# CITestShield.net
KiCad netlist of a schematic drawn in EAGLE
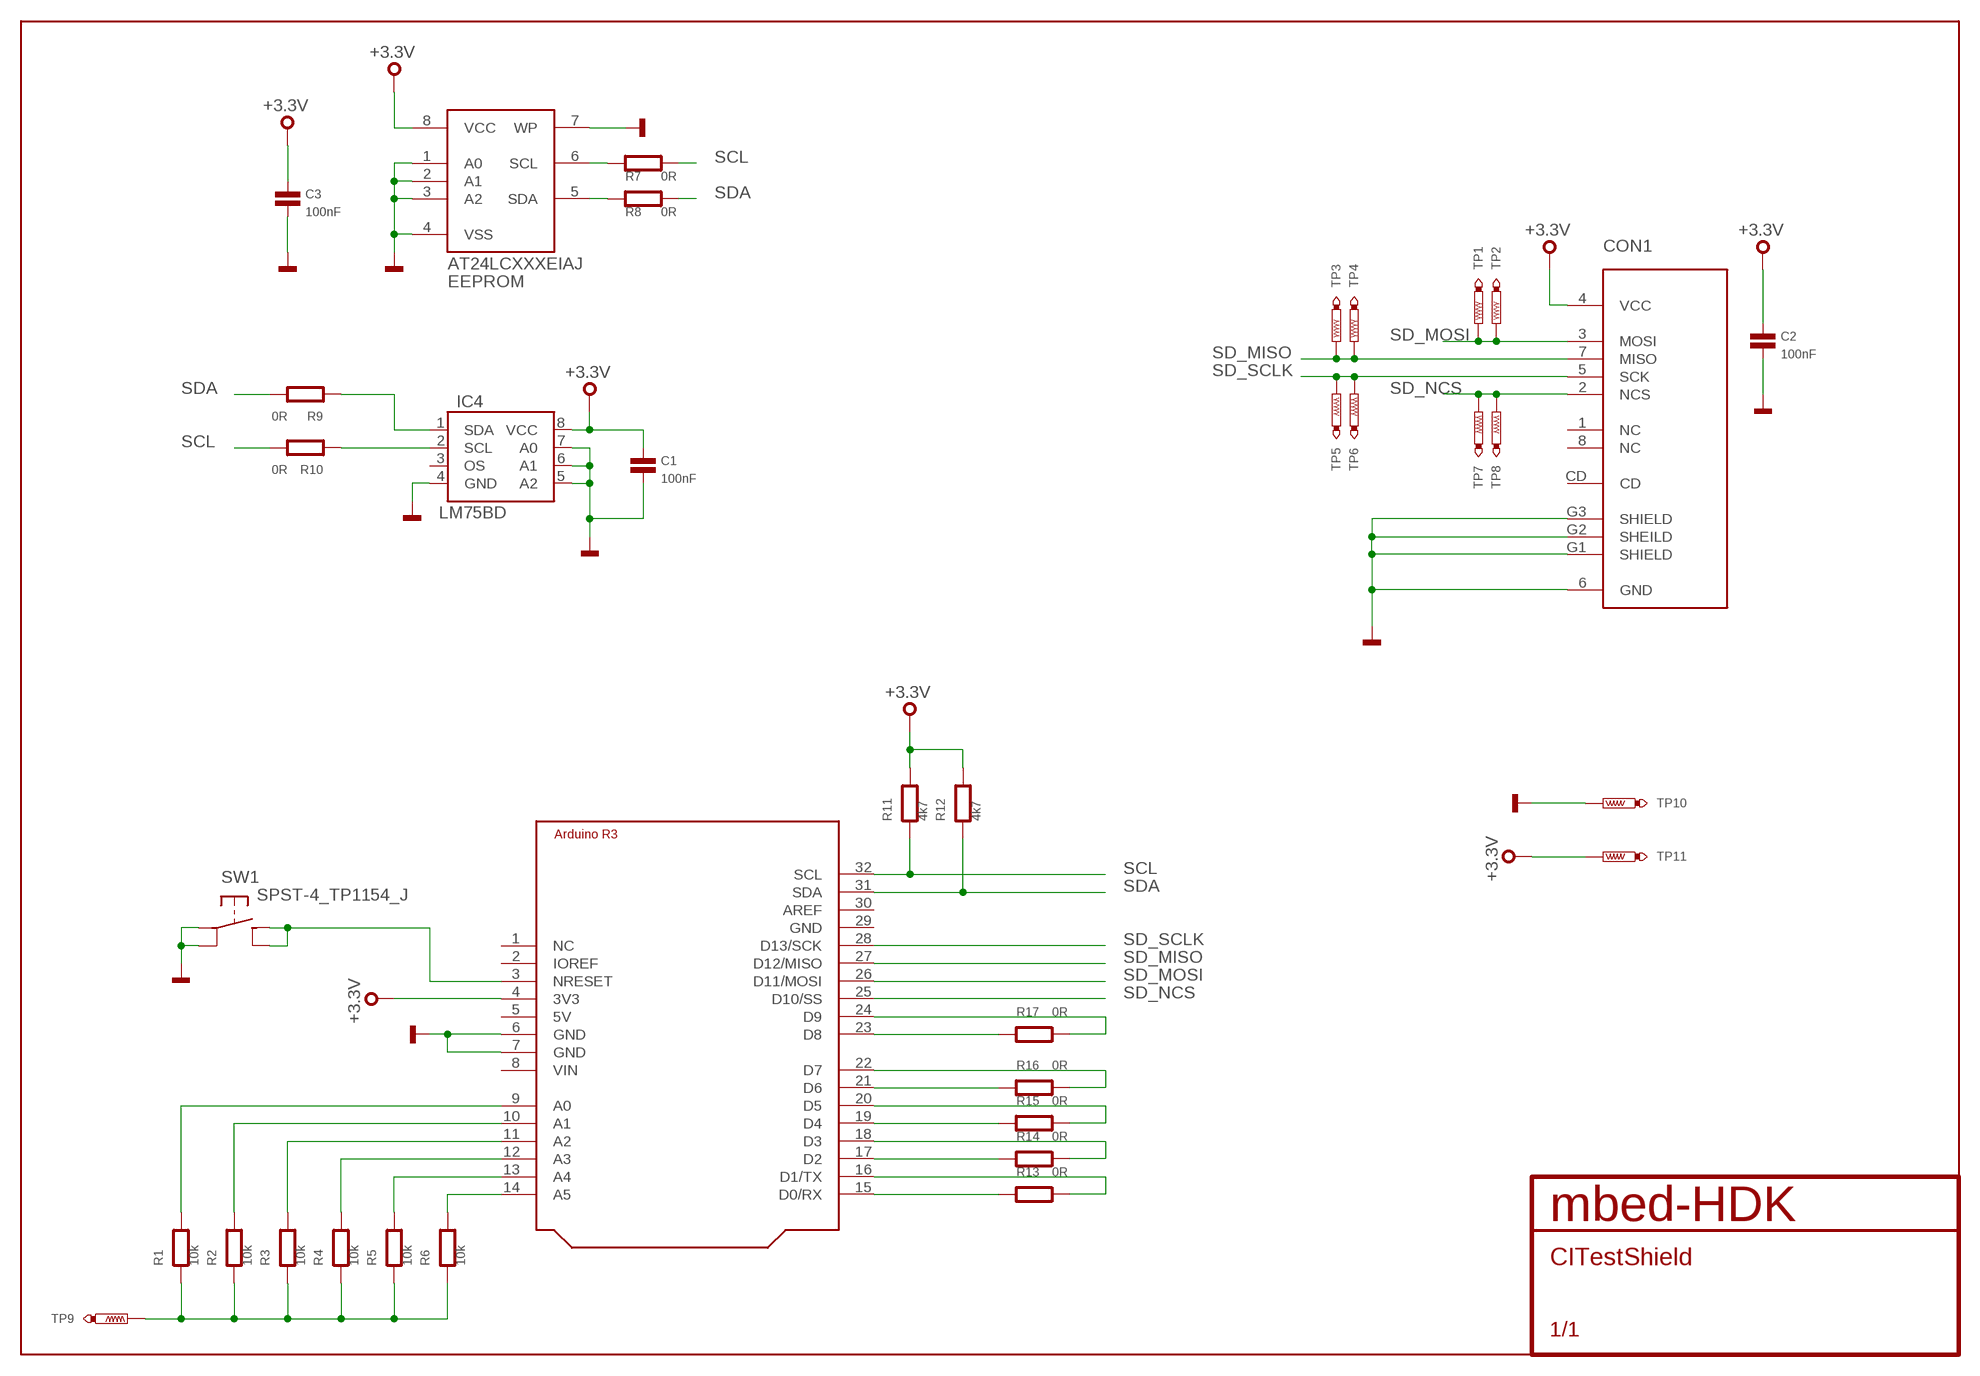
[diagram p0: schematic, sheet 1]

(export (version "E")
  (design (tool "Eeschema 10.0.6"))
  (components
    (comp (ref "BRD1")
      (value "ARDUINO-R3_SILK")
      (footprint "eagle-import:ARDUINO-R3-SILK")
      (libsource (lib "eagle-import") (part "ARDUINO-R3_SILK"))
    )
    (comp (ref "C1")
      (value "100nF")
      (footprint "eagle-import:0603")
      (libsource (lib "eagle-import") (part "C0603"))
    )
    (comp (ref "C2")
      (value "100nF")
      (footprint "eagle-import:0603")
      (libsource (lib "eagle-import") (part "C0603"))
    )
    (comp (ref "C3")
      (value "100nF")
      (footprint "eagle-import:0603")
      (libsource (lib "eagle-import") (part "C0603"))
    )
    (comp (ref "CON1")
      (value "MICRO-SD")
      (footprint "eagle-import:AMPHENOL-101-00660-68-6")
      (libsource (lib "eagle-import") (part "MICRO-SD"))
    )
    (comp (ref "EEPROM")
      (value "AT24LCXXXEIAJ")
      (footprint "eagle-import:SO08-EIAJ")
      (libsource (lib "eagle-import") (part "AT24LCXXXEIAJ"))
    )
    (comp (ref "IC4")
      (value "LM75BD")
      (footprint "eagle-import:SO8")
      (libsource (lib "eagle-import") (part "LM75BD"))
    )
    (comp (ref "R1")
      (value "10k")
      (footprint "eagle-import:0603")
      (libsource (lib "eagle-import") (part "R0603"))
    )
    (comp (ref "R2")
      (value "10k")
      (footprint "eagle-import:0603")
      (libsource (lib "eagle-import") (part "R0603"))
    )
    (comp (ref "R3")
      (value "10k")
      (footprint "eagle-import:0603")
      (libsource (lib "eagle-import") (part "R0603"))
    )
    (comp (ref "R4")
      (value "10k")
      (footprint "eagle-import:0603")
      (libsource (lib "eagle-import") (part "R0603"))
    )
    (comp (ref "R5")
      (value "10k")
      (footprint "eagle-import:0603")
      (libsource (lib "eagle-import") (part "R0603"))
    )
    (comp (ref "R6")
      (value "10k")
      (footprint "eagle-import:0603")
      (libsource (lib "eagle-import") (part "R0603"))
    )
    (comp (ref "R7")
      (value "0R")
      (footprint "eagle-import:0603")
      (libsource (lib "eagle-import") (part "R0603"))
    )
    (comp (ref "R8")
      (value "0R")
      (footprint "eagle-import:0603")
      (libsource (lib "eagle-import") (part "R0603"))
    )
    (comp (ref "R9")
      (value "0R")
      (footprint "eagle-import:0603")
      (libsource (lib "eagle-import") (part "R0603"))
    )
    (comp (ref "R10")
      (value "0R")
      (footprint "eagle-import:0603")
      (libsource (lib "eagle-import") (part "R0603"))
    )
    (comp (ref "R11")
      (value "4k7")
      (footprint "eagle-import:0603")
      (libsource (lib "eagle-import") (part "R0603"))
    )
    (comp (ref "R12")
      (value "4k7")
      (footprint "eagle-import:0603")
      (libsource (lib "eagle-import") (part "R0603"))
    )
    (comp (ref "R13")
      (value "0R")
      (footprint "eagle-import:0603")
      (libsource (lib "eagle-import") (part "R0603"))
    )
    (comp (ref "R14")
      (value "0R")
      (footprint "eagle-import:0603")
      (libsource (lib "eagle-import") (part "R0603"))
    )
    (comp (ref "R15")
      (value "0R")
      (footprint "eagle-import:0603")
      (libsource (lib "eagle-import") (part "R0603"))
    )
    (comp (ref "R16")
      (value "0R")
      (footprint "eagle-import:0603")
      (libsource (lib "eagle-import") (part "R0603"))
    )
    (comp (ref "R17")
      (value "0R")
      (footprint "eagle-import:0603")
      (libsource (lib "eagle-import") (part "R0603"))
    )
    (comp (ref "SW1")
      (value "SPST-4_TP1154_J")
      (footprint "eagle-import:TP-1154X")
      (libsource (lib "eagle-import") (part "SPST-4_TP1154_J"))
    )
    (comp (ref "TP1")
      (value "TEST-POINT-50R-SMD")
      (footprint "eagle-import:TP50-SMD")
      (libsource (lib "eagle-import") (part "TEST-POINT-50R-SMD"))
    )
    (comp (ref "TP2")
      (value "TEST-POINT-50R-SMD")
      (footprint "eagle-import:TP50-SMD")
      (libsource (lib "eagle-import") (part "TEST-POINT-50R-SMD"))
    )
    (comp (ref "TP3")
      (value "TEST-POINT-50R-SMD")
      (footprint "eagle-import:TP50-SMD")
      (libsource (lib "eagle-import") (part "TEST-POINT-50R-SMD"))
    )
    (comp (ref "TP4")
      (value "TEST-POINT-50R-SMD")
      (footprint "eagle-import:TP50-SMD")
      (libsource (lib "eagle-import") (part "TEST-POINT-50R-SMD"))
    )
    (comp (ref "TP5")
      (value "TEST-POINT-50R-SMD")
      (footprint "eagle-import:TP50-SMD")
      (libsource (lib "eagle-import") (part "TEST-POINT-50R-SMD"))
    )
    (comp (ref "TP6")
      (value "TEST-POINT-50R-SMD")
      (footprint "eagle-import:TP50-SMD")
      (libsource (lib "eagle-import") (part "TEST-POINT-50R-SMD"))
    )
    (comp (ref "TP7")
      (value "TEST-POINT-50R-SMD")
      (footprint "eagle-import:TP50-SMD")
      (libsource (lib "eagle-import") (part "TEST-POINT-50R-SMD"))
    )
    (comp (ref "TP8")
      (value "TEST-POINT-50R-SMD")
      (footprint "eagle-import:TP50-SMD")
      (libsource (lib "eagle-import") (part "TEST-POINT-50R-SMD"))
    )
    (comp (ref "TP9")
      (value "TEST-POINT-50R-SMD")
      (footprint "eagle-import:TP50-SMD")
      (libsource (lib "eagle-import") (part "TEST-POINT-50R-SMD"))
    )
    (comp (ref "TP10")
      (value "TEST-POINT-50R-SMD")
      (footprint "eagle-import:TP50-SMD")
      (libsource (lib "eagle-import") (part "TEST-POINT-50R-SMD"))
    )
    (comp (ref "TP11")
      (value "TEST-POINT-50R-SMD")
      (footprint "eagle-import:TP50-SMD")
      (libsource (lib "eagle-import") (part "TEST-POINT-50R-SMD"))
    )
  )
  (nets
    (net (code "1") (name "+3.3V") (class "Default")
      (node (ref "BRD1") (pin "4") (pinfunction "3V3_4") (pintype "bidirectional"))
      (node (ref "C1") (pin "1") (pinfunction "P$1_1") (pintype "passive"))
      (node (ref "C2") (pin "1") (pinfunction "P$1_1") (pintype "passive"))
      (node (ref "C3") (pin "1") (pinfunction "P$1_1") (pintype "passive"))
      (node (ref "CON1") (pin "4") (pinfunction "VCC_4") (pintype "bidirectional"))
      (node (ref "EEPROM") (pin "8") (pinfunction "VCC_8") (pintype "power_in"))
      (node (ref "IC4") (pin "8") (pinfunction "VCC_8") (pintype "bidirectional"))
      (node (ref "R11") (pin "2") (pinfunction "P$2_2") (pintype "passive"))
      (node (ref "R12") (pin "2") (pinfunction "P$2_2") (pintype "passive"))
      (node (ref "TP11") (pin "TP") (pinfunction "TP_TP") (pintype "input"))
    )
    (net (code "2") (name "/SCL") (class "Default")
      (node (ref "BRD1") (pin "32") (pinfunction "SCL_32") (pintype "bidirectional"))
      (node (ref "R10") (pin "2") (pinfunction "P$2_2") (pintype "passive"))
      (node (ref "R11") (pin "1") (pinfunction "P$1_1") (pintype "passive"))
      (node (ref "R7") (pin "2") (pinfunction "P$2_2") (pintype "passive"))
    )
    (net (code "3") (name "/SDA") (class "Default")
      (node (ref "BRD1") (pin "31") (pinfunction "SDA_31") (pintype "bidirectional"))
      (node (ref "R12") (pin "1") (pinfunction "P$1_1") (pintype "passive"))
      (node (ref "R8") (pin "2") (pinfunction "P$2_2") (pintype "passive"))
      (node (ref "R9") (pin "2") (pinfunction "P$2_2") (pintype "passive"))
    )
    (net (code "4") (name "/SD_MISO") (class "Default")
      (node (ref "BRD1") (pin "27") (pinfunction "D12/MISO_27") (pintype "bidirectional"))
      (node (ref "CON1") (pin "7") (pinfunction "MISO_7") (pintype "bidirectional"))
      (node (ref "TP3") (pin "TP") (pinfunction "TP_TP") (pintype "input"))
      (node (ref "TP4") (pin "TP") (pinfunction "TP_TP") (pintype "input"))
    )
    (net (code "5") (name "/SD_MOSI") (class "Default")
      (node (ref "BRD1") (pin "26") (pinfunction "D11/MOSI_26") (pintype "bidirectional"))
      (node (ref "CON1") (pin "3") (pinfunction "MOSI_3") (pintype "bidirectional"))
      (node (ref "TP1") (pin "TP") (pinfunction "TP_TP") (pintype "input"))
      (node (ref "TP2") (pin "TP") (pinfunction "TP_TP") (pintype "input"))
    )
    (net (code "6") (name "/SD_NCS") (class "Default")
      (node (ref "BRD1") (pin "25") (pinfunction "D10/SS_25") (pintype "bidirectional"))
      (node (ref "CON1") (pin "2") (pinfunction "NCS_2") (pintype "bidirectional"))
      (node (ref "TP7") (pin "TP") (pinfunction "TP_TP") (pintype "input"))
      (node (ref "TP8") (pin "TP") (pinfunction "TP_TP") (pintype "input"))
    )
    (net (code "7") (name "/SD_SCLK") (class "Default")
      (node (ref "BRD1") (pin "28") (pinfunction "D13/SCK_28") (pintype "bidirectional"))
      (node (ref "CON1") (pin "5") (pinfunction "SCK_5") (pintype "bidirectional"))
      (node (ref "TP5") (pin "TP") (pinfunction "TP_TP") (pintype "input"))
      (node (ref "TP6") (pin "TP") (pinfunction "TP_TP") (pintype "input"))
    )
    (net (code "8") (name "GND") (class "Default")
      (node (ref "BRD1") (pin "6") (pinfunction "GND_6") (pintype "bidirectional"))
      (node (ref "BRD1") (pin "7") (pinfunction "GND_7") (pintype "bidirectional"))
      (node (ref "C1") (pin "2") (pinfunction "P$2_2") (pintype "passive"))
      (node (ref "C2") (pin "2") (pinfunction "P$2_2") (pintype "passive"))
      (node (ref "C3") (pin "2") (pinfunction "P$2_2") (pintype "passive"))
      (node (ref "CON1") (pin "6") (pinfunction "GND_6") (pintype "bidirectional"))
      (node (ref "CON1") (pin "G1") (pinfunction "SHIELD_G1") (pintype "bidirectional"))
      (node (ref "CON1") (pin "G2") (pinfunction "SHEILD_G2") (pintype "bidirectional"))
      (node (ref "CON1") (pin "G3") (pinfunction "SHIELD_G3") (pintype "bidirectional"))
      (node (ref "EEPROM") (pin "1") (pinfunction "A0_1") (pintype "bidirectional"))
      (node (ref "EEPROM") (pin "2") (pinfunction "A1_2") (pintype "bidirectional"))
      (node (ref "EEPROM") (pin "3") (pinfunction "A2_3") (pintype "bidirectional"))
      (node (ref "EEPROM") (pin "4") (pinfunction "VSS_4") (pintype "power_in"))
      (node (ref "EEPROM") (pin "7") (pinfunction "WP_7") (pintype "bidirectional"))
      (node (ref "IC4") (pin "4") (pinfunction "GND_4") (pintype "bidirectional"))
      (node (ref "IC4") (pin "5") (pinfunction "A2_5") (pintype "bidirectional"))
      (node (ref "IC4") (pin "6") (pinfunction "A1_6") (pintype "bidirectional"))
      (node (ref "IC4") (pin "7") (pinfunction "A0_7") (pintype "bidirectional"))
      (node (ref "SW1") (pin "A1") (pinfunction "A1_A1") (pintype "passive"))
      (node (ref "SW1") (pin "A2") (pinfunction "A2_A2") (pintype "passive"))
      (node (ref "TP10") (pin "TP") (pinfunction "TP_TP") (pintype "input"))
    )
    (net (code "9") (name "Net-(BRD1-A0)") (class "Default")
      (node (ref "BRD1") (pin "9") (pinfunction "A0_9") (pintype "bidirectional"))
      (node (ref "R1") (pin "2") (pinfunction "P$2_2") (pintype "passive"))
    )
    (net (code "10") (name "Net-(BRD1-A1)") (class "Default")
      (node (ref "BRD1") (pin "10") (pinfunction "A1_10") (pintype "bidirectional"))
      (node (ref "R2") (pin "2") (pinfunction "P$2_2") (pintype "passive"))
    )
    (net (code "11") (name "Net-(BRD1-A2)") (class "Default")
      (node (ref "BRD1") (pin "11") (pinfunction "A2_11") (pintype "bidirectional"))
      (node (ref "R3") (pin "2") (pinfunction "P$2_2") (pintype "passive"))
    )
    (net (code "12") (name "Net-(BRD1-A3)") (class "Default")
      (node (ref "BRD1") (pin "12") (pinfunction "A3_12") (pintype "bidirectional"))
      (node (ref "R4") (pin "2") (pinfunction "P$2_2") (pintype "passive"))
    )
    (net (code "13") (name "Net-(BRD1-A4)") (class "Default")
      (node (ref "BRD1") (pin "13") (pinfunction "A4_13") (pintype "bidirectional"))
      (node (ref "R5") (pin "2") (pinfunction "P$2_2") (pintype "passive"))
    )
    (net (code "14") (name "Net-(BRD1-A5)") (class "Default")
      (node (ref "BRD1") (pin "14") (pinfunction "A5_14") (pintype "bidirectional"))
      (node (ref "R6") (pin "2") (pinfunction "P$2_2") (pintype "passive"))
    )
    (net (code "15") (name "Net-(BRD1-D0{slash}RX)") (class "Default")
      (node (ref "BRD1") (pin "15") (pinfunction "D0/RX_15") (pintype "bidirectional"))
      (node (ref "R13") (pin "1") (pinfunction "P$1_1") (pintype "passive"))
    )
    (net (code "16") (name "Net-(BRD1-D1{slash}TX)") (class "Default")
      (node (ref "BRD1") (pin "16") (pinfunction "D1/TX_16") (pintype "bidirectional"))
      (node (ref "R13") (pin "2") (pinfunction "P$2_2") (pintype "passive"))
    )
    (net (code "17") (name "Net-(BRD1-D2)") (class "Default")
      (node (ref "BRD1") (pin "17") (pinfunction "D2_17") (pintype "bidirectional"))
      (node (ref "R14") (pin "1") (pinfunction "P$1_1") (pintype "passive"))
    )
    (net (code "18") (name "Net-(BRD1-D3)") (class "Default")
      (node (ref "BRD1") (pin "18") (pinfunction "D3_18") (pintype "bidirectional"))
      (node (ref "R14") (pin "2") (pinfunction "P$2_2") (pintype "passive"))
    )
    (net (code "19") (name "Net-(BRD1-D4)") (class "Default")
      (node (ref "BRD1") (pin "19") (pinfunction "D4_19") (pintype "bidirectional"))
      (node (ref "R15") (pin "1") (pinfunction "P$1_1") (pintype "passive"))
    )
    (net (code "20") (name "Net-(BRD1-D5)") (class "Default")
      (node (ref "BRD1") (pin "20") (pinfunction "D5_20") (pintype "bidirectional"))
      (node (ref "R15") (pin "2") (pinfunction "P$2_2") (pintype "passive"))
    )
    (net (code "21") (name "Net-(BRD1-D6)") (class "Default")
      (node (ref "BRD1") (pin "21") (pinfunction "D6_21") (pintype "bidirectional"))
      (node (ref "R16") (pin "1") (pinfunction "P$1_1") (pintype "passive"))
    )
    (net (code "22") (name "Net-(BRD1-D7)") (class "Default")
      (node (ref "BRD1") (pin "22") (pinfunction "D7_22") (pintype "bidirectional"))
      (node (ref "R16") (pin "2") (pinfunction "P$2_2") (pintype "passive"))
    )
    (net (code "23") (name "Net-(BRD1-D8)") (class "Default")
      (node (ref "BRD1") (pin "23") (pinfunction "D8_23") (pintype "bidirectional"))
      (node (ref "R17") (pin "1") (pinfunction "P$1_1") (pintype "passive"))
    )
    (net (code "24") (name "Net-(BRD1-D9)") (class "Default")
      (node (ref "BRD1") (pin "24") (pinfunction "D9_24") (pintype "bidirectional"))
      (node (ref "R17") (pin "2") (pinfunction "P$2_2") (pintype "passive"))
    )
    (net (code "25") (name "Net-(BRD1-NRESET)") (class "Default")
      (node (ref "BRD1") (pin "3") (pinfunction "NRESET_3") (pintype "bidirectional"))
      (node (ref "SW1") (pin "B1") (pinfunction "B1_B1") (pintype "passive"))
      (node (ref "SW1") (pin "B2") (pinfunction "B2_B2") (pintype "passive"))
    )
    (net (code "26") (name "Net-(EEPROM-SCL)") (class "Default")
      (node (ref "EEPROM") (pin "6") (pinfunction "SCL_6") (pintype "bidirectional"))
      (node (ref "R7") (pin "1") (pinfunction "P$1_1") (pintype "passive"))
    )
    (net (code "27") (name "Net-(EEPROM-SDA)") (class "Default")
      (node (ref "EEPROM") (pin "5") (pinfunction "SDA_5") (pintype "bidirectional"))
      (node (ref "R8") (pin "1") (pinfunction "P$1_1") (pintype "passive"))
    )
    (net (code "28") (name "Net-(IC4-SCL)") (class "Default")
      (node (ref "IC4") (pin "2") (pinfunction "SCL_2") (pintype "bidirectional"))
      (node (ref "R10") (pin "1") (pinfunction "P$1_1") (pintype "passive"))
    )
    (net (code "29") (name "Net-(IC4-SDA)") (class "Default")
      (node (ref "IC4") (pin "1") (pinfunction "SDA_1") (pintype "bidirectional"))
      (node (ref "R9") (pin "1") (pinfunction "P$1_1") (pintype "passive"))
    )
    (net (code "30") (name "Net-(R1-P$1)") (class "Default")
      (node (ref "R1") (pin "1") (pinfunction "P$1_1") (pintype "passive"))
      (node (ref "R2") (pin "1") (pinfunction "P$1_1") (pintype "passive"))
      (node (ref "R3") (pin "1") (pinfunction "P$1_1") (pintype "passive"))
      (node (ref "R4") (pin "1") (pinfunction "P$1_1") (pintype "passive"))
      (node (ref "R5") (pin "1") (pinfunction "P$1_1") (pintype "passive"))
      (node (ref "R6") (pin "1") (pinfunction "P$1_1") (pintype "passive"))
      (node (ref "TP9") (pin "TP") (pinfunction "TP_TP") (pintype "input"))
    )
    (net (code "31") (name "unconnected-(BRD1-5V-Pad5)") (class "Default")
      (node (ref "BRD1") (pin "5") (pinfunction "5V_5") (pintype "bidirectional"))
    )
    (net (code "32") (name "unconnected-(BRD1-AREF-Pad30)") (class "Default")
      (node (ref "BRD1") (pin "30") (pinfunction "AREF_30") (pintype "bidirectional"))
    )
    (net (code "33") (name "unconnected-(BRD1-GND-Pad29)") (class "Default")
      (node (ref "BRD1") (pin "29") (pinfunction "GND_29") (pintype "bidirectional"))
    )
    (net (code "34") (name "unconnected-(BRD1-IOREF-Pad2)") (class "Default")
      (node (ref "BRD1") (pin "2") (pinfunction "IOREF_2") (pintype "bidirectional"))
    )
    (net (code "35") (name "unconnected-(BRD1-NC-Pad1)") (class "Default")
      (node (ref "BRD1") (pin "1") (pinfunction "NC_1") (pintype "bidirectional"))
    )
    (net (code "36") (name "unconnected-(BRD1-VIN-Pad8)") (class "Default")
      (node (ref "BRD1") (pin "8") (pinfunction "VIN_8") (pintype "bidirectional"))
    )
    (net (code "37") (name "unconnected-(CON1-NC-Pad1)") (class "Default")
      (node (ref "CON1") (pin "1") (pinfunction "NC_1") (pintype "bidirectional"))
    )
    (net (code "38") (name "unconnected-(CON1-NC-Pad8)") (class "Default")
      (node (ref "CON1") (pin "8") (pinfunction "NC_8") (pintype "bidirectional"))
    )
    (net (code "39") (name "unconnected-(CON1-PadCD)") (class "Default")
      (node (ref "CON1") (pin "CD") (pinfunction "CD_CD") (pintype "bidirectional"))
    )
    (net (code "40") (name "unconnected-(IC4-OS-Pad3)") (class "Default")
      (node (ref "IC4") (pin "3") (pinfunction "OS_3") (pintype "bidirectional"))
    )
  )
)
